# FOC_Driver.net
KiCad netlist of a schematic drawn in Altium Designer
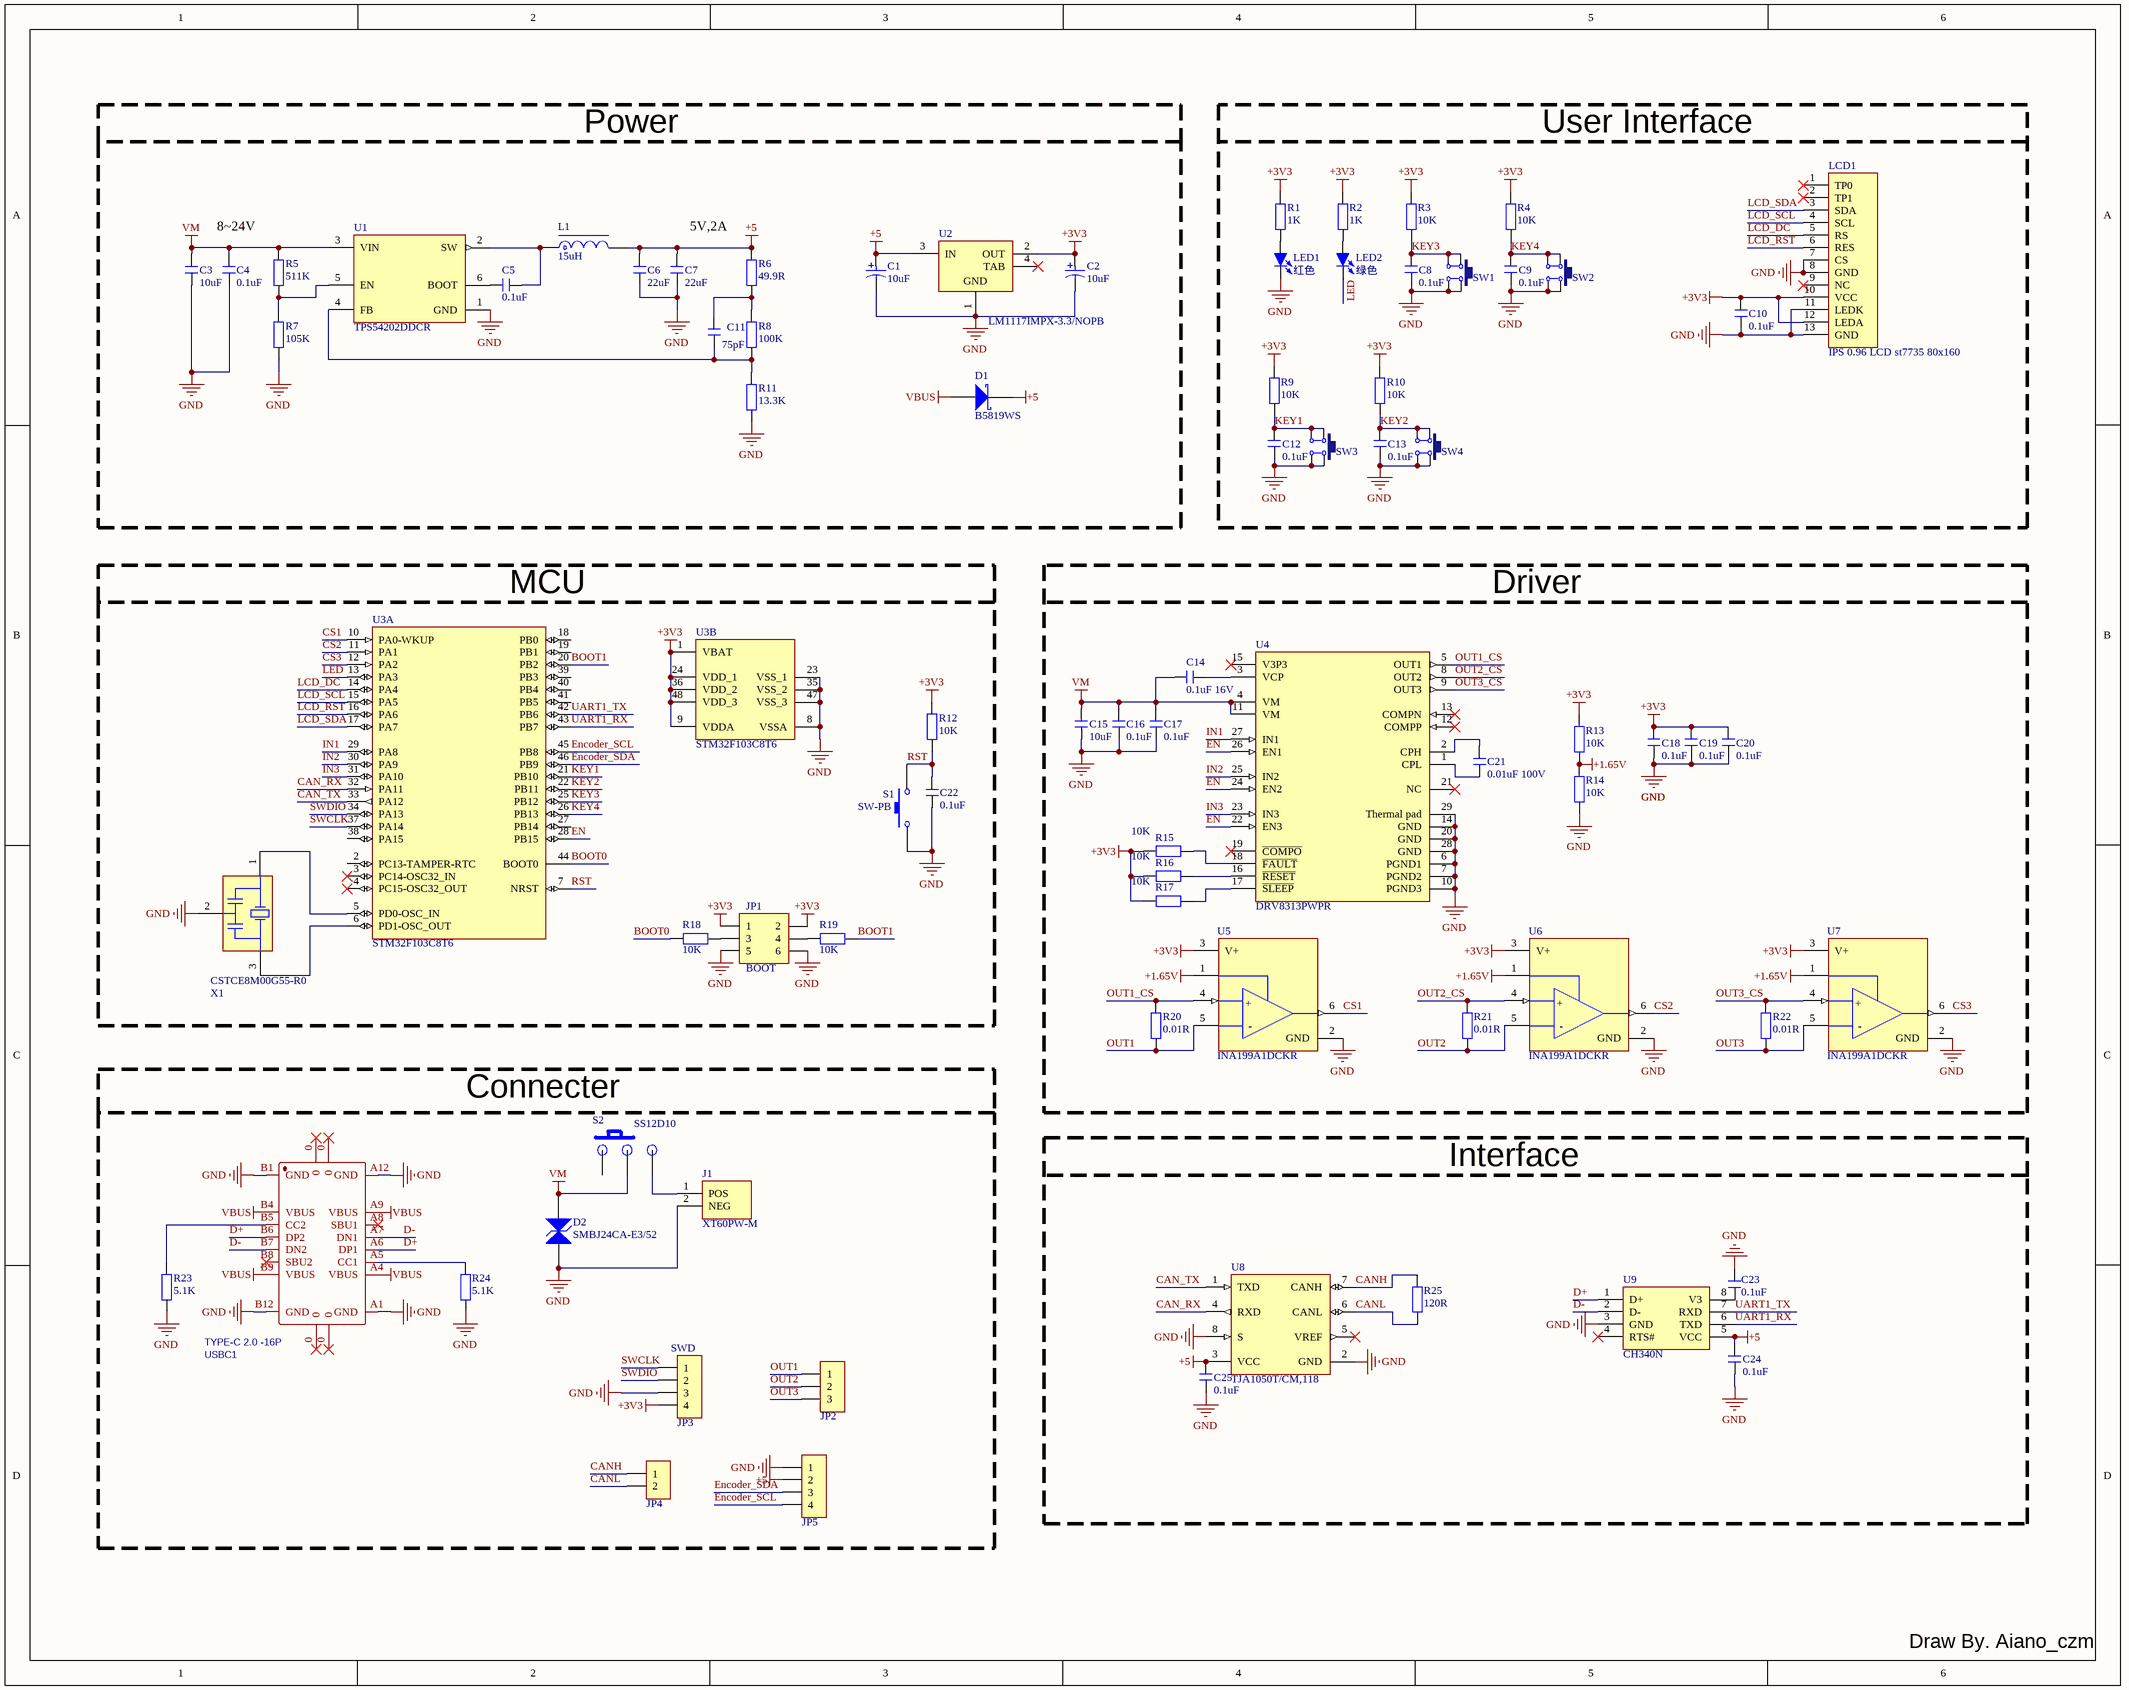
[diagram p0: FOC_Driver.SchDoc]

(export (version "E")
  (design (tool "Eeschema 10.0.6"))
  (components
    (comp (ref "C1")
      (value "10uF")
      (footprint "CAPMP3217X18-T_V")
      (description "Standard Tantalum, 10 uF, +/- 10%, 16 V, -55 to 125 degC, 2-Pin SMD (1206), RoHS, Tape and Reel")
      (libsource (lib "Altium Content Vault") (part "CAP-P-2"))
    )
    (comp (ref "C2")
      (value "10uF")
      (footprint "CAPMP3217X18-T_V")
      (description "Standard Tantalum, 10 uF, +/- 10%, 16 V, -55 to 125 degC, 2-Pin SMD (1206), RoHS, Tape and Reel")
      (libsource (lib "Altium Content Vault") (part "CAP-P-2"))
    )
    (comp (ref "C3")
      (value "10uF")
      (footprint "C 1206_M")
      (description "贴片电容")
      (libsource (lib "0.1 - 电阻-电容-电感") (part "C"))
    )
    (comp (ref "C4")
      (value "0.1uF")
      (footprint "C 0603_M")
      (description "贴片电容")
      (libsource (lib "0.1 - 电阻-电容-电感") (part "C"))
    )
    (comp (ref "C5")
      (value "0.1uF")
      (footprint "C 0603_M")
      (description "贴片电容")
      (libsource (lib "0.1 - 电阻-电容-电感") (part "C"))
    )
    (comp (ref "C6")
      (value "22uF")
      (footprint "C 1206_M")
      (description "贴片电容")
      (libsource (lib "0.1 - 电阻-电容-电感") (part "C"))
    )
    (comp (ref "C7")
      (value "22uF")
      (footprint "C 1206_M")
      (description "贴片电容")
      (libsource (lib "0.1 - 电阻-电容-电感") (part "C"))
    )
    (comp (ref "C8")
      (value "0.1uF")
      (footprint "C 0603_M")
      (description "贴片电容")
      (libsource (lib "0.1 - 电阻-电容-电感") (part "C"))
    )
    (comp (ref "C9")
      (value "0.1uF")
      (footprint "C 0603_M")
      (description "贴片电容")
      (libsource (lib "0.1 - 电阻-电容-电感") (part "C"))
    )
    (comp (ref "C10")
      (value "0.1uF")
      (footprint "C 0603_M")
      (description "贴片电容")
      (libsource (lib "0.1 - 电阻-电容-电感") (part "C"))
    )
    (comp (ref "C11")
      (value "75pF")
      (footprint "C 0603_M")
      (description "贴片电容")
      (libsource (lib "0.1 - 电阻-电容-电感") (part "C"))
    )
    (comp (ref "C12")
      (value "0.1uF")
      (footprint "C 0603_M")
      (description "贴片电容")
      (libsource (lib "0.1 - 电阻-电容-电感") (part "C"))
    )
    (comp (ref "C13")
      (value "0.1uF")
      (footprint "C 0603_M")
      (description "贴片电容")
      (libsource (lib "0.1 - 电阻-电容-电感") (part "C"))
    )
    (comp (ref "C14")
      (value "0.1uF 16V")
      (footprint "C 0603_M")
      (description "贴片电容")
      (libsource (lib "0.1 - 电阻-电容-电感") (part "C"))
    )
    (comp (ref "C15")
      (value "10uF")
      (footprint "C 1206_M")
      (description "贴片电容")
      (libsource (lib "0.1 - 电阻-电容-电感") (part "C"))
    )
    (comp (ref "C16")
      (value "0.1uF")
      (footprint "C 0603_M")
      (description "贴片电容")
      (libsource (lib "0.1 - 电阻-电容-电感") (part "C"))
    )
    (comp (ref "C17")
      (value "0.1uF")
      (footprint "C 0603_M")
      (description "贴片电容")
      (libsource (lib "0.1 - 电阻-电容-电感") (part "C"))
    )
    (comp (ref "C18")
      (value "0.1uF")
      (footprint "C 0603_M")
      (description "贴片电容")
      (libsource (lib "0.1 - 电阻-电容-电感") (part "C"))
    )
    (comp (ref "C19")
      (value "0.1uF")
      (footprint "C 0603_M")
      (description "贴片电容")
      (libsource (lib "0.1 - 电阻-电容-电感") (part "C"))
    )
    (comp (ref "C20")
      (value "0.1uF")
      (footprint "C 0603_M")
      (description "贴片电容")
      (libsource (lib "0.1 - 电阻-电容-电感") (part "C"))
    )
    (comp (ref "C21")
      (value "0.01uF 100V")
      (footprint "C 0603_M")
      (description "贴片电容")
      (libsource (lib "0.1 - 电阻-电容-电感") (part "C"))
    )
    (comp (ref "C22")
      (value "0.1uF")
      (footprint "C 0603_L")
      (description "贴片电容")
      (libsource (lib "0.1 - 电阻-电容-电感") (part "C"))
    )
    (comp (ref "C23")
      (value "0.1uF")
      (footprint "C 0603_M")
      (description "贴片电容")
      (libsource (lib "0.1 - 电阻-电容-电感") (part "C"))
    )
    (comp (ref "C24")
      (value "0.1uF")
      (footprint "C 0603_M")
      (description "贴片电容")
      (libsource (lib "0.1 - 电阻-电容-电感") (part "C"))
    )
    (comp (ref "C25")
      (value "0.1uF")
      (footprint "C 0603_M")
      (description "贴片电容")
      (libsource (lib "0.1 - 电阻-电容-电感") (part "C"))
    )
    (comp (ref "D1")
      (value "B5819WS")
      (footprint "SOD-323")
      (description "肖特基二极管")
      (libsource (lib "0.2 - 二极管-整流桥") (part "1N5819"))
    )
    (comp (ref "D2")
      (value "SMBJ24CA-E3/52")
      (footprint "VISH-DO-214AA-A-2_V")
      (fields (field (name "MANUFACTURER") "Vishay"))
      (libsource (lib "Altium Content Vault") (part "DZEN-AA-2"))
    )
    (comp (ref "J1")
      (value "XT60PW-M")
      (footprint "AMASS_XT60PW-M")
      (description "Socket, DC supply, male, PIN: 2")
      (fields (field (name "MF") "AMASS"))
      (libsource (lib "接插件") (part "XT60PW-M"))
    )
    (comp (ref "JP1")
      (value "BOOT")
      (footprint "HDR2.54-LI-2x3P")
      (description "3*2P接插件")
      (fields (field (name "版权归属") "封装库来自淘宝 ID：黄晶宝石"))
      (libsource (lib "5.4 - 接插件-脚距2.54 (100mil) ") (part "Header 3X2"))
    )
    (comp (ref "JP2")
      (value "HDR-1X3")
      (footprint "KF301-5.0-3P")
      (description "3P接插件")
      (fields (field (name "版权归属") "封装库来自淘宝 ID：黄晶宝石"))
      (libsource (lib "6.0 - 接插件-脚距5.0") (part "Header 3"))
    )
    (comp (ref "JP3")
      (value "SWD")
      (footprint "HDR2.54-LI-4P")
      (description "4P接插件")
      (fields (field (name "版权归属") "封装库来自淘宝 ID：黄晶宝石"))
      (libsource (lib "5.4 - 接插件-脚距2.54 (100mil) ") (part "Header 4"))
    )
    (comp (ref "JP4")
      (value "HDR-1X2")
      (footprint "KF301-5.0-2P")
      (description "2P接插件")
      (fields (field (name "版权归属") "封装库来自淘宝 ID：黄晶宝石"))
      (libsource (lib "6.0 - 接插件-脚距5.0") (part "Header 2"))
    )
    (comp (ref "JP5")
      (value "HDR-1X4")
      (footprint "HDR2.54-M-LI-4P")
      (description "4P接插件")
      (fields (field (name "版权归属") "封装库来自淘宝 ID：黄晶宝石"))
      (libsource (lib "5.4 - 接插件-脚距2.54 (100mil) ") (part "Header 4"))
    )
    (comp (ref "L1")
      (value "15uH")
      (footprint "CDRH73")
      (description "功率屏蔽电感")
      (fields (field (name "版权归属") "封装库来自淘宝 ID：黄晶宝石"))
      (libsource (lib "0.1 - 电阻-电容-电感") (part "L-CDRH"))
    )
    (comp (ref "LCD1")
      (value "IPS 0.96 LCD st7735 80x160")
      (footprint "IPS 0.96 LCD st7735 80x160")
      (description "中景园全彩IPS SPI接口 160x80 LCD显示屏")
      (libsource (lib "显示屏") (part "IPS 0.96 LCD st7735 80x160"))
    )
    (comp (ref "LED1")
      (value "红色")
      (footprint "LED 0603R")
      (description "贴片LED")
      (fields (field (name "版权归属") "封装库来自淘宝 ID：黄晶宝石"))
      (libsource (lib "0.3 - LED发光二极管") (part "LED-SMD"))
    )
    (comp (ref "LED2")
      (value "绿色")
      (footprint "LED 0603R")
      (description "贴片LED")
      (fields (field (name "版权归属") "封装库来自淘宝 ID：黄晶宝石"))
      (libsource (lib "0.3 - LED发光二极管") (part "LED-SMD"))
    )
    (comp (ref "R1")
      (value "1K")
      (footprint "R 0603_M")
      (description "贴片电阻")
      (fields (field (name "版权归属") "来自淘宝 ID：黄晶宝石"))
      (libsource (lib "0.1 - 电阻-电容-电感") (part "R"))
    )
    (comp (ref "R2")
      (value "1K")
      (footprint "R 0603_M")
      (description "贴片电阻")
      (fields (field (name "版权归属") "来自淘宝 ID：黄晶宝石"))
      (libsource (lib "0.1 - 电阻-电容-电感") (part "R"))
    )
    (comp (ref "R3")
      (value "10K")
      (footprint "R 0603_M")
      (description "贴片电阻")
      (fields (field (name "版权归属") "来自淘宝 ID：黄晶宝石"))
      (libsource (lib "0.1 - 电阻-电容-电感") (part "R"))
    )
    (comp (ref "R4")
      (value "10K")
      (footprint "R 0603_M")
      (description "贴片电阻")
      (fields (field (name "版权归属") "来自淘宝 ID：黄晶宝石"))
      (libsource (lib "0.1 - 电阻-电容-电感") (part "R"))
    )
    (comp (ref "R5")
      (value "511K")
      (footprint "R 0603_M")
      (description "贴片电阻")
      (fields (field (name "版权归属") "来自淘宝 ID：黄晶宝石"))
      (libsource (lib "0.1 - 电阻-电容-电感") (part "R"))
    )
    (comp (ref "R6")
      (value "49.9R")
      (footprint "R 0603_M")
      (description "贴片电阻")
      (fields (field (name "版权归属") "来自淘宝 ID：黄晶宝石"))
      (libsource (lib "0.1 - 电阻-电容-电感") (part "R"))
    )
    (comp (ref "R7")
      (value "105K")
      (footprint "R 0603_M")
      (description "贴片电阻")
      (fields (field (name "版权归属") "来自淘宝 ID：黄晶宝石"))
      (libsource (lib "0.1 - 电阻-电容-电感") (part "R"))
    )
    (comp (ref "R8")
      (value "100K")
      (footprint "R 0603_M")
      (description "贴片电阻")
      (fields (field (name "版权归属") "来自淘宝 ID：黄晶宝石"))
      (libsource (lib "0.1 - 电阻-电容-电感") (part "R"))
    )
    (comp (ref "R9")
      (value "10K")
      (footprint "R 0603_M")
      (description "贴片电阻")
      (fields (field (name "版权归属") "来自淘宝 ID：黄晶宝石"))
      (libsource (lib "0.1 - 电阻-电容-电感") (part "R"))
    )
    (comp (ref "R10")
      (value "10K")
      (footprint "R 0603_M")
      (description "贴片电阻")
      (fields (field (name "版权归属") "来自淘宝 ID：黄晶宝石"))
      (libsource (lib "0.1 - 电阻-电容-电感") (part "R"))
    )
    (comp (ref "R11")
      (value "13.3K")
      (footprint "R 0603_M")
      (description "贴片电阻")
      (fields (field (name "版权归属") "来自淘宝 ID：黄晶宝石"))
      (libsource (lib "0.1 - 电阻-电容-电感") (part "R"))
    )
    (comp (ref "R12")
      (value "10K")
      (footprint "R 0603_M")
      (description "贴片电阻")
      (fields (field (name "版权归属") "来自淘宝 ID：黄晶宝石"))
      (libsource (lib "0.1 - 电阻-电容-电感") (part "R"))
    )
    (comp (ref "R13")
      (value "10K")
      (footprint "R 0603_M")
      (description "贴片电阻")
      (fields (field (name "版权归属") "来自淘宝 ID：黄晶宝石"))
      (libsource (lib "0.1 - 电阻-电容-电感") (part "R"))
    )
    (comp (ref "R14")
      (value "10K")
      (footprint "R 0603_M")
      (description "贴片电阻")
      (fields (field (name "版权归属") "来自淘宝 ID：黄晶宝石"))
      (libsource (lib "0.1 - 电阻-电容-电感") (part "R"))
    )
    (comp (ref "R15")
      (value "10K")
      (footprint "R 0603_M")
      (description "贴片电阻")
      (fields (field (name "版权归属") "来自淘宝 ID：黄晶宝石"))
      (libsource (lib "0.1 - 电阻-电容-电感") (part "R"))
    )
    (comp (ref "R16")
      (value "10K")
      (footprint "R 0603_M")
      (description "贴片电阻")
      (fields (field (name "版权归属") "来自淘宝 ID：黄晶宝石"))
      (libsource (lib "0.1 - 电阻-电容-电感") (part "R"))
    )
    (comp (ref "R17")
      (value "10K")
      (footprint "R 0603_M")
      (description "贴片电阻")
      (fields (field (name "版权归属") "来自淘宝 ID：黄晶宝石"))
      (libsource (lib "0.1 - 电阻-电容-电感") (part "R"))
    )
    (comp (ref "R18")
      (value "10K")
      (footprint "R 0603_M")
      (description "贴片电阻")
      (fields (field (name "版权归属") "来自淘宝 ID：黄晶宝石"))
      (libsource (lib "0.1 - 电阻-电容-电感") (part "R"))
    )
    (comp (ref "R19")
      (value "10K")
      (footprint "R 0603_M")
      (description "贴片电阻")
      (fields (field (name "版权归属") "来自淘宝 ID：黄晶宝石"))
      (libsource (lib "0.1 - 电阻-电容-电感") (part "R"))
    )
    (comp (ref "R20")
      (value "0.01R")
      (footprint "R 0805_M")
      (description "贴片电阻")
      (fields (field (name "版权归属") "来自淘宝 ID：黄晶宝石"))
      (libsource (lib "0.1 - 电阻-电容-电感") (part "R"))
    )
    (comp (ref "R21")
      (value "0.01R")
      (footprint "R 0805_M")
      (description "贴片电阻")
      (fields (field (name "版权归属") "来自淘宝 ID：黄晶宝石"))
      (libsource (lib "0.1 - 电阻-电容-电感") (part "R"))
    )
    (comp (ref "R22")
      (value "0.01R")
      (footprint "R 0805_M")
      (description "贴片电阻")
      (fields (field (name "版权归属") "来自淘宝 ID：黄晶宝石"))
      (libsource (lib "0.1 - 电阻-电容-电感") (part "R"))
    )
    (comp (ref "R23")
      (value "5.1K")
      (footprint "R 0603_M")
      (description "贴片电阻")
      (fields (field (name "版权归属") "来自淘宝 ID：黄晶宝石"))
      (libsource (lib "0.1 - 电阻-电容-电感") (part "R"))
    )
    (comp (ref "R24")
      (value "5.1K")
      (footprint "R 0603_M")
      (description "贴片电阻")
      (fields (field (name "版权归属") "来自淘宝 ID：黄晶宝石"))
      (libsource (lib "0.1 - 电阻-电容-电感") (part "R"))
    )
    (comp (ref "R25")
      (value "120R")
      (footprint "R 0603_M")
      (description "贴片电阻")
      (fields (field (name "版权归属") "来自淘宝 ID：黄晶宝石"))
      (libsource (lib "0.1 - 电阻-电容-电感") (part "R"))
    )
    (comp (ref "S1")
      (value "SW-PB")
      (footprint "SW_PB2_A1")
      (description "微动开关")
      (fields (field (name "PUBLISHER") "Altium Limited"))
      (libsource (lib "0.7 - 常用按键-开关") (part "SW-PB"))
    )
    (comp (ref "S2")
      (value "SS12D10")
      (footprint "SS12D10")
      (description "大电流拨动开关 直脚")
      (libsource (lib "开关") (part "SS12D10"))
    )
    (comp (ref "SW1")
      (value "6x6x5")
      (footprint "TSW SMD-6*6*4.3")
      (description "贴片6x6轻触开关")
      (fields (field (name "版权归属") "封装库来自淘宝 ID：黄晶宝石"))
      (libsource (lib "0.7 - 常用按键-开关") (part "TSW SMD-6x6"))
    )
    (comp (ref "SW2")
      (value "6x6x5")
      (footprint "TSW SMD-6*6*4.3")
      (description "贴片6x6轻触开关")
      (fields (field (name "版权归属") "封装库来自淘宝 ID：黄晶宝石"))
      (libsource (lib "0.7 - 常用按键-开关") (part "TSW SMD-6x6"))
    )
    (comp (ref "SW3")
      (value "6x6x5")
      (footprint "TSW SMD-6*6*4.3")
      (description "贴片6x6轻触开关")
      (fields (field (name "版权归属") "封装库来自淘宝 ID：黄晶宝石"))
      (libsource (lib "0.7 - 常用按键-开关") (part "TSW SMD-6x6"))
    )
    (comp (ref "SW4")
      (value "6x6x5")
      (footprint "TSW SMD-6*6*4.3")
      (description "贴片6x6轻触开关")
      (fields (field (name "版权归属") "封装库来自淘宝 ID：黄晶宝石"))
      (libsource (lib "0.7 - 常用按键-开关") (part "TSW SMD-6x6"))
    )
    (comp (ref "U1")
      (value "TPS54202DDCR")
      (footprint "FP-DDC0006A-IPC_B")
      (description "IC REG BUCK ADJ 2A TSOT23-6")
      (libsource (lib "Altium Content Vault") (part "35c2d3f1afc239a386b2ba50eead654"))
    )
    (comp (ref "U2")
      (value "LM1117IMPX-3.3/NOPB")
      (footprint "MP04A_M")
      (description "800mA Low-Dropout Linear Regulator, 4-pin SOT-223, Pb-Free")
      (fields (field (name "MANUFACTURER") "National Semiconductor"))
      (libsource (lib "Altium Content Vault") (part "PM-REG-LM1086-SOT4"))
    )
    (comp (ref "U3")
      (value "STM32F103C8T6")
      (footprint "STM-LQFP48_M")
      (libsource (lib "Altium Content Vault") (part "MC-ARM-STM32F103X8_B-SQ48"))
    )
    (comp (ref "U4")
      (value "DRV8313PWPR")
      (footprint "FP-PWP0028C-IPC_B")
      (description "IC MOTOR DRIVER 8V-60V 28HTSSOP")
      (libsource (lib "Altium Content Vault") (part "6c5e8d1d79df7918d4eb9ae5de6b4b8"))
    )
    (comp (ref "U5")
      (value "INA199A1DCKR")
      (footprint "FP-DCK0006A-IPC_A")
      (description "IC OPAMP CURR SENSE 14KHZ SC70-6")
      (libsource (lib "Altium Content Vault") (part "e49a1c4e02aaa7cdc8fdf8d536a06ae"))
    )
    (comp (ref "U6")
      (value "INA199A1DCKR")
      (footprint "FP-DCK0006A-IPC_A")
      (description "IC OPAMP CURR SENSE 14KHZ SC70-6")
      (libsource (lib "Altium Content Vault") (part "e49a1c4e02aaa7cdc8fdf8d536a06ae"))
    )
    (comp (ref "U7")
      (value "INA199A1DCKR")
      (footprint "FP-DCK0006A-IPC_A")
      (description "IC OPAMP CURR SENSE 14KHZ SC70-6")
      (libsource (lib "Altium Content Vault") (part "e49a1c4e02aaa7cdc8fdf8d536a06ae"))
    )
    (comp (ref "U8")
      (value "TJA1050T/CM,118")
      (footprint "NXP-SOT96-1_M")
      (fields (field (name "MANUFACTURER") "NXP Semiconductors"))
      (libsource (lib "Altium Content Vault") (part "NXP-TJA1050-8"))
    )
    (comp (ref "U9") (value "CH340N") (footprint "CH340N") (libsource (lib "接口芯片") (part "CH340N")))
    (comp (ref "USBC1")
      (value "TYPE-C 2.0 -16P")
      (footprint "USB-C-SMD_TYPE-C-USB-5")
      (description "USB2.0 Type-C 母座 16Pin")
      (libsource (lib "0.8 - 以太网-音频-USB插座") (part "USB2.0 Type-C 16Pin母座"))
    )
    (comp (ref "X1")
      (value "CSTCE8M00G55-R0")
      (footprint "MURA-CSTCE_G_A-3_V")
      (description "Ceramic Resonator, 8 MHz, +/- 0.5%, -20 to 80 degC, 3-Pin SMD, RoHS, Tape and Reel")
      (fields (field (name "TOLERANCE") "0.5%") (field (name "MANUFACTURER") "Murata"))
      (libsource (lib "Altium Content Vault") (part "MURA-CSTCE_G_A-3"))
    )
  )
  (nets
    (net (code "1") (name "+1.65V") (class "Default")
      (node (ref "R13") (pin "1") (pinfunction "1_1") (pintype "passive"))
      (node (ref "R14") (pin "2") (pinfunction "2_2") (pintype "passive"))
      (node (ref "U5") (pin "1") (pinfunction "REF_1") (pintype "passive"))
      (node (ref "U6") (pin "1") (pinfunction "REF_1") (pintype "passive"))
      (node (ref "U7") (pin "1") (pinfunction "REF_1") (pintype "passive"))
    )
    (net (code "2") (name "+3V3") (class "Default")
      (node (ref "C10") (pin "2") (pinfunction "2_2") (pintype "passive"))
      (node (ref "C18") (pin "1") (pinfunction "1_1") (pintype "passive"))
      (node (ref "C19") (pin "1") (pinfunction "1_1") (pintype "passive"))
      (node (ref "C2") (pin "1") (pinfunction "1_1") (pintype "passive"))
      (node (ref "C20") (pin "1") (pinfunction "1_1") (pintype "passive"))
      (node (ref "JP1") (pin "1") (pinfunction "1_1") (pintype "passive"))
      (node (ref "JP1") (pin "2") (pinfunction "2_2") (pintype "passive"))
      (node (ref "JP3") (pin "4") (pinfunction "4_4") (pintype "passive"))
      (node (ref "LCD1") (pin "10") (pinfunction "VCC_10") (pintype "passive"))
      (node (ref "LCD1") (pin "12") (pinfunction "LEDA_12") (pintype "passive"))
      (node (ref "R1") (pin "1") (pinfunction "1_1") (pintype "passive"))
      (node (ref "R10") (pin "1") (pinfunction "1_1") (pintype "passive"))
      (node (ref "R12") (pin "2") (pinfunction "2_2") (pintype "passive"))
      (node (ref "R13") (pin "2") (pinfunction "2_2") (pintype "passive"))
      (node (ref "R15") (pin "2") (pinfunction "2_2") (pintype "passive"))
      (node (ref "R16") (pin "2") (pinfunction "2_2") (pintype "passive"))
      (node (ref "R17") (pin "2") (pinfunction "2_2") (pintype "passive"))
      (node (ref "R2") (pin "1") (pinfunction "1_1") (pintype "passive"))
      (node (ref "R3") (pin "1") (pinfunction "1_1") (pintype "passive"))
      (node (ref "R4") (pin "1") (pinfunction "1_1") (pintype "passive"))
      (node (ref "R9") (pin "1") (pinfunction "1_1") (pintype "passive"))
      (node (ref "U2") (pin "2") (pinfunction "OUT_2") (pintype "power_in"))
      (node (ref "U3") (pin "1") (pinfunction "VBAT_1") (pintype "power_in"))
      (node (ref "U3") (pin "24") (pinfunction "VDD_1_24") (pintype "power_in"))
      (node (ref "U3") (pin "36") (pinfunction "VDD_2_36") (pintype "power_in"))
      (node (ref "U3") (pin "48") (pinfunction "VDD_3_48") (pintype "power_in"))
      (node (ref "U3") (pin "9") (pinfunction "VDDA_9") (pintype "power_in"))
      (node (ref "U5") (pin "3") (pinfunction "V+_3") (pintype "power_in"))
      (node (ref "U6") (pin "3") (pinfunction "V+_3") (pintype "power_in"))
      (node (ref "U7") (pin "3") (pinfunction "V+_3") (pintype "power_in"))
    )
    (net (code "3") (name "+5") (class "Default")
      (node (ref "C1") (pin "1") (pinfunction "1_1") (pintype "passive"))
      (node (ref "C24") (pin "2") (pinfunction "2_2") (pintype "passive"))
      (node (ref "C25") (pin "1") (pinfunction "1_1") (pintype "passive"))
      (node (ref "C6") (pin "2") (pinfunction "2_2") (pintype "passive"))
      (node (ref "C7") (pin "2") (pinfunction "2_2") (pintype "passive"))
      (node (ref "D1") (pin "2") (pinfunction "K_2") (pintype "passive"))
      (node (ref "JP5") (pin "2") (pinfunction "2_2") (pintype "passive"))
      (node (ref "L1") (pin "2") (pinfunction "2_2") (pintype "passive"))
      (node (ref "R6") (pin "2") (pinfunction "2_2") (pintype "passive"))
      (node (ref "U2") (pin "3") (pinfunction "IN_3") (pintype "power_in"))
      (node (ref "U8") (pin "3") (pinfunction "VCC_3") (pintype "power_in"))
      (node (ref "U9") (pin "5") (pinfunction "VCC_5") (pintype "passive"))
    )
    (net (code "4") (name "/BOOT0") (class "Default")
      (node (ref "R18") (pin "2") (pinfunction "2_2") (pintype "passive"))
      (node (ref "U3") (pin "44") (pinfunction "BOOT0_44") (pintype "passive"))
    )
    (net (code "5") (name "/BOOT1") (class "Default")
      (node (ref "R19") (pin "1") (pinfunction "1_1") (pintype "passive"))
      (node (ref "U3") (pin "20") (pinfunction "PB2_20") (pintype "bidirectional"))
    )
    (net (code "6") (name "/CANH") (class "Default")
      (node (ref "JP4") (pin "1") (pinfunction "1_1") (pintype "passive"))
      (node (ref "R25") (pin "2") (pinfunction "2_2") (pintype "passive"))
      (node (ref "U8") (pin "7") (pinfunction "CANH_7") (pintype "bidirectional"))
    )
    (net (code "7") (name "/CANL") (class "Default")
      (node (ref "JP4") (pin "2") (pinfunction "2_2") (pintype "passive"))
      (node (ref "R25") (pin "1") (pinfunction "1_1") (pintype "passive"))
      (node (ref "U8") (pin "6") (pinfunction "CANL_6") (pintype "bidirectional"))
    )
    (net (code "8") (name "/CAN_RX") (class "Default")
      (node (ref "U3") (pin "32") (pinfunction "PA11_32") (pintype "input"))
      (node (ref "U8") (pin "4") (pinfunction "RXD_4") (pintype "output"))
    )
    (net (code "9") (name "/CAN_TX") (class "Default")
      (node (ref "U3") (pin "33") (pinfunction "PA12_33") (pintype "output"))
      (node (ref "U8") (pin "1") (pinfunction "TXD_1") (pintype "input"))
    )
    (net (code "10") (name "/CS1") (class "Default")
      (node (ref "U3") (pin "10") (pinfunction "PA0-WKUP_10") (pintype "input"))
      (node (ref "U5") (pin "6") (pinfunction "OUT_6") (pintype "output"))
    )
    (net (code "11") (name "/CS2") (class "Default")
      (node (ref "U3") (pin "11") (pinfunction "PA1_11") (pintype "input"))
      (node (ref "U6") (pin "6") (pinfunction "OUT_6") (pintype "output"))
    )
    (net (code "12") (name "/CS3") (class "Default")
      (node (ref "U3") (pin "12") (pinfunction "PA2_12") (pintype "input"))
      (node (ref "U7") (pin "6") (pinfunction "OUT_6") (pintype "output"))
    )
    (net (code "13") (name "/D+") (class "Default")
      (node (ref "U9") (pin "1") (pinfunction "D+_1") (pintype "passive"))
      (node (ref "USBC1") (pin "A6") (pinfunction "DP1_A6") (pintype "passive"))
      (node (ref "USBC1") (pin "B6") (pinfunction "DP2_B6") (pintype "passive"))
    )
    (net (code "14") (name "/D-") (class "Default")
      (node (ref "U9") (pin "2") (pinfunction "D-_2") (pintype "passive"))
      (node (ref "USBC1") (pin "A7") (pinfunction "DN1_A7") (pintype "passive"))
      (node (ref "USBC1") (pin "B7") (pinfunction "DN2_B7") (pintype "passive"))
    )
    (net (code "15") (name "/EN") (class "Default")
      (node (ref "U3") (pin "28") (pinfunction "PB15_28") (pintype "bidirectional"))
      (node (ref "U4") (pin "22") (pinfunction "EN3_22") (pintype "input"))
      (node (ref "U4") (pin "24") (pinfunction "EN2_24") (pintype "input"))
      (node (ref "U4") (pin "26") (pinfunction "EN1_26") (pintype "input"))
    )
    (net (code "16") (name "/Encoder_SCL") (class "Default")
      (node (ref "JP5") (pin "4") (pinfunction "4_4") (pintype "passive"))
      (node (ref "U3") (pin "45") (pinfunction "PB8_45") (pintype "bidirectional"))
    )
    (net (code "17") (name "/Encoder_SDA") (class "Default")
      (node (ref "JP5") (pin "3") (pinfunction "3_3") (pintype "passive"))
      (node (ref "U3") (pin "46") (pinfunction "PB9_46") (pintype "bidirectional"))
    )
    (net (code "18") (name "/IN1") (class "Default")
      (node (ref "U3") (pin "29") (pinfunction "PA8_29") (pintype "bidirectional"))
      (node (ref "U4") (pin "27") (pinfunction "IN1_27") (pintype "input"))
    )
    (net (code "19") (name "/IN2") (class "Default")
      (node (ref "U3") (pin "30") (pinfunction "PA9_30") (pintype "bidirectional"))
      (node (ref "U4") (pin "25") (pinfunction "IN2_25") (pintype "input"))
    )
    (net (code "20") (name "/IN3") (class "Default")
      (node (ref "U3") (pin "31") (pinfunction "PA10_31") (pintype "bidirectional"))
      (node (ref "U4") (pin "23") (pinfunction "IN3_23") (pintype "input"))
    )
    (net (code "21") (name "/KEY1") (class "Default")
      (node (ref "C12") (pin "1") (pinfunction "1_1") (pintype "passive"))
      (node (ref "R9") (pin "2") (pinfunction "2_2") (pintype "passive"))
      (node (ref "SW3") (pin "1") (pinfunction "1_1") (pintype "passive"))
      (node (ref "SW3") (pin "4") (pinfunction "4_4") (pintype "passive"))
      (node (ref "U3") (pin "21") (pinfunction "PB10_21") (pintype "bidirectional"))
    )
    (net (code "22") (name "/KEY2") (class "Default")
      (node (ref "C13") (pin "1") (pinfunction "1_1") (pintype "passive"))
      (node (ref "R10") (pin "2") (pinfunction "2_2") (pintype "passive"))
      (node (ref "SW4") (pin "1") (pinfunction "1_1") (pintype "passive"))
      (node (ref "SW4") (pin "4") (pinfunction "4_4") (pintype "passive"))
      (node (ref "U3") (pin "22") (pinfunction "PB11_22") (pintype "bidirectional"))
    )
    (net (code "23") (name "/KEY3") (class "Default")
      (node (ref "C8") (pin "1") (pinfunction "1_1") (pintype "passive"))
      (node (ref "R3") (pin "2") (pinfunction "2_2") (pintype "passive"))
      (node (ref "SW1") (pin "1") (pinfunction "1_1") (pintype "passive"))
      (node (ref "SW1") (pin "4") (pinfunction "4_4") (pintype "passive"))
      (node (ref "U3") (pin "25") (pinfunction "PB12_25") (pintype "bidirectional"))
    )
    (net (code "24") (name "/KEY4") (class "Default")
      (node (ref "C9") (pin "1") (pinfunction "1_1") (pintype "passive"))
      (node (ref "R4") (pin "2") (pinfunction "2_2") (pintype "passive"))
      (node (ref "SW2") (pin "1") (pinfunction "1_1") (pintype "passive"))
      (node (ref "SW2") (pin "4") (pinfunction "4_4") (pintype "passive"))
      (node (ref "U3") (pin "26") (pinfunction "PB13_26") (pintype "bidirectional"))
    )
    (net (code "25") (name "/LCD_DC") (class "Default")
      (node (ref "LCD1") (pin "5") (pinfunction "RS_5") (pintype "passive"))
      (node (ref "U3") (pin "14") (pinfunction "PA4_14") (pintype "bidirectional"))
    )
    (net (code "26") (name "/LCD_RST") (class "Default")
      (node (ref "LCD1") (pin "6") (pinfunction "RES_6") (pintype "passive"))
      (node (ref "U3") (pin "16") (pinfunction "PA6_16") (pintype "bidirectional"))
    )
    (net (code "27") (name "/LCD_SCL") (class "Default")
      (node (ref "LCD1") (pin "4") (pinfunction "SCL_4") (pintype "passive"))
      (node (ref "U3") (pin "15") (pinfunction "PA5_15") (pintype "bidirectional"))
    )
    (net (code "28") (name "/LCD_SDA") (class "Default")
      (node (ref "LCD1") (pin "3") (pinfunction "SDA_3") (pintype "passive"))
      (node (ref "U3") (pin "17") (pinfunction "PA7_17") (pintype "bidirectional"))
    )
    (net (code "29") (name "/LED") (class "Default")
      (node (ref "LED2") (pin "2") (pinfunction "K_2") (pintype "passive"))
      (node (ref "U3") (pin "13") (pinfunction "PA3_13") (pintype "bidirectional"))
    )
    (net (code "30") (name "/OUT1") (class "Default")
      (node (ref "JP2") (pin "1") (pinfunction "1_1") (pintype "passive"))
      (node (ref "R20") (pin "1") (pinfunction "1_1") (pintype "passive"))
      (node (ref "U5") (pin "5") (pinfunction "IN-_5") (pintype "passive"))
    )
    (net (code "31") (name "/OUT1_CS") (class "Default")
      (node (ref "R20") (pin "2") (pinfunction "2_2") (pintype "passive"))
      (node (ref "U4") (pin "5") (pinfunction "OUT1_5") (pintype "output"))
      (node (ref "U5") (pin "4") (pinfunction "IN+_4") (pintype "input"))
    )
    (net (code "32") (name "/OUT2") (class "Default")
      (node (ref "JP2") (pin "2") (pinfunction "2_2") (pintype "passive"))
      (node (ref "R21") (pin "1") (pinfunction "1_1") (pintype "passive"))
      (node (ref "U6") (pin "5") (pinfunction "IN-_5") (pintype "passive"))
    )
    (net (code "33") (name "/OUT2_CS") (class "Default")
      (node (ref "R21") (pin "2") (pinfunction "2_2") (pintype "passive"))
      (node (ref "U4") (pin "8") (pinfunction "OUT2_8") (pintype "output"))
      (node (ref "U6") (pin "4") (pinfunction "IN+_4") (pintype "input"))
    )
    (net (code "34") (name "/OUT3") (class "Default")
      (node (ref "JP2") (pin "3") (pinfunction "3_3") (pintype "passive"))
      (node (ref "R22") (pin "1") (pinfunction "1_1") (pintype "passive"))
      (node (ref "U7") (pin "5") (pinfunction "IN-_5") (pintype "passive"))
    )
    (net (code "35") (name "/OUT3_CS") (class "Default")
      (node (ref "R22") (pin "2") (pinfunction "2_2") (pintype "passive"))
      (node (ref "U4") (pin "9") (pinfunction "OUT3_9") (pintype "output"))
      (node (ref "U7") (pin "4") (pinfunction "IN+_4") (pintype "input"))
    )
    (net (code "36") (name "/RST") (class "Default")
      (node (ref "C22") (pin "2") (pinfunction "2_2") (pintype "passive"))
      (node (ref "R12") (pin "1") (pinfunction "1_1") (pintype "passive"))
      (node (ref "S1") (pin "2") (pinfunction "2_2") (pintype "passive"))
      (node (ref "U3") (pin "7") (pinfunction "NRST_7") (pintype "bidirectional"))
    )
    (net (code "37") (name "/SWCLK") (class "Default")
      (node (ref "JP3") (pin "1") (pinfunction "1_1") (pintype "passive"))
      (node (ref "U3") (pin "37") (pinfunction "PA14_37") (pintype "bidirectional"))
    )
    (net (code "38") (name "/SWDIO") (class "Default")
      (node (ref "JP3") (pin "2") (pinfunction "2_2") (pintype "passive"))
      (node (ref "U3") (pin "34") (pinfunction "PA13_34") (pintype "bidirectional"))
    )
    (net (code "39") (name "/UART1_RX") (class "Default")
      (node (ref "U3") (pin "43") (pinfunction "PB7_43") (pintype "bidirectional"))
      (node (ref "U9") (pin "6") (pinfunction "TXD_6") (pintype "passive"))
    )
    (net (code "40") (name "/UART1_TX") (class "Default")
      (node (ref "U3") (pin "42") (pinfunction "PB6_42") (pintype "bidirectional"))
      (node (ref "U9") (pin "7") (pinfunction "RXD_7") (pintype "passive"))
    )
    (net (code "41") (name "GND") (class "Default")
      (node (ref "C1") (pin "2") (pinfunction "2_2") (pintype "passive"))
      (node (ref "C10") (pin "1") (pinfunction "1_1") (pintype "passive"))
      (node (ref "C12") (pin "2") (pinfunction "2_2") (pintype "passive"))
      (node (ref "C13") (pin "2") (pinfunction "2_2") (pintype "passive"))
      (node (ref "C15") (pin "1") (pinfunction "1_1") (pintype "passive"))
      (node (ref "C16") (pin "1") (pinfunction "1_1") (pintype "passive"))
      (node (ref "C17") (pin "1") (pinfunction "1_1") (pintype "passive"))
      (node (ref "C18") (pin "2") (pinfunction "2_2") (pintype "passive"))
      (node (ref "C19") (pin "2") (pinfunction "2_2") (pintype "passive"))
      (node (ref "C2") (pin "2") (pinfunction "2_2") (pintype "passive"))
      (node (ref "C20") (pin "2") (pinfunction "2_2") (pintype "passive"))
      (node (ref "C22") (pin "1") (pinfunction "1_1") (pintype "passive"))
      (node (ref "C23") (pin "2") (pinfunction "2_2") (pintype "passive"))
      (node (ref "C24") (pin "1") (pinfunction "1_1") (pintype "passive"))
      (node (ref "C25") (pin "2") (pinfunction "2_2") (pintype "passive"))
      (node (ref "C3") (pin "1") (pinfunction "1_1") (pintype "passive"))
      (node (ref "C4") (pin "1") (pinfunction "1_1") (pintype "passive"))
      (node (ref "C6") (pin "1") (pinfunction "1_1") (pintype "passive"))
      (node (ref "C7") (pin "1") (pinfunction "1_1") (pintype "passive"))
      (node (ref "C8") (pin "2") (pinfunction "2_2") (pintype "passive"))
      (node (ref "C9") (pin "2") (pinfunction "2_2") (pintype "passive"))
      (node (ref "D2") (pin "1") (pinfunction "A_1") (pintype "passive"))
      (node (ref "J1") (pin "2") (pinfunction "NEG_2") (pintype "passive"))
      (node (ref "JP1") (pin "5") (pinfunction "5_5") (pintype "passive"))
      (node (ref "JP1") (pin "6") (pinfunction "6_6") (pintype "passive"))
      (node (ref "JP3") (pin "3") (pinfunction "3_3") (pintype "passive"))
      (node (ref "JP5") (pin "1") (pinfunction "1_1") (pintype "passive"))
      (node (ref "LCD1") (pin "11") (pinfunction "LEDK_11") (pintype "passive"))
      (node (ref "LCD1") (pin "13") (pinfunction "GND_13") (pintype "passive"))
      (node (ref "LCD1") (pin "7") (pinfunction "CS_7") (pintype "passive"))
      (node (ref "LCD1") (pin "8") (pinfunction "GND_8") (pintype "passive"))
      (node (ref "LED1") (pin "2") (pinfunction "K_2") (pintype "passive"))
      (node (ref "R11") (pin "1") (pinfunction "1_1") (pintype "passive"))
      (node (ref "R14") (pin "1") (pinfunction "1_1") (pintype "passive"))
      (node (ref "R23") (pin "1") (pinfunction "1_1") (pintype "passive"))
      (node (ref "R24") (pin "1") (pinfunction "1_1") (pintype "passive"))
      (node (ref "R7") (pin "1") (pinfunction "1_1") (pintype "passive"))
      (node (ref "S1") (pin "1") (pinfunction "1_1") (pintype "passive"))
      (node (ref "SW1") (pin "2") (pinfunction "2_2") (pintype "passive"))
      (node (ref "SW1") (pin "3") (pinfunction "3_3") (pintype "passive"))
      (node (ref "SW2") (pin "2") (pinfunction "2_2") (pintype "passive"))
      (node (ref "SW2") (pin "3") (pinfunction "3_3") (pintype "passive"))
      (node (ref "SW3") (pin "2") (pinfunction "2_2") (pintype "passive"))
      (node (ref "SW3") (pin "3") (pinfunction "3_3") (pintype "passive"))
      (node (ref "SW4") (pin "2") (pinfunction "2_2") (pintype "passive"))
      (node (ref "SW4") (pin "3") (pinfunction "3_3") (pintype "passive"))
      (node (ref "U1") (pin "1") (pinfunction "GND_1") (pintype "power_in"))
      (node (ref "U2") (pin "1") (pinfunction "GND_1") (pintype "power_in"))
      (node (ref "U3") (pin "23") (pinfunction "VSS_1_23") (pintype "power_in"))
      (node (ref "U3") (pin "35") (pinfunction "VSS_2_35") (pintype "power_in"))
      (node (ref "U3") (pin "47") (pinfunction "VSS_3_47") (pintype "power_in"))
      (node (ref "U3") (pin "8") (pinfunction "VSSA_8") (pintype "power_in"))
      (node (ref "U4") (pin "10") (pinfunction "PGND3_10") (pintype "power_in"))
      (node (ref "U4") (pin "14") (pinfunction "GND_14") (pintype "power_in"))
      (node (ref "U4") (pin "20") (pinfunction "GND_20") (pintype "power_in"))
      (node (ref "U4") (pin "28") (pinfunction "GND_28") (pintype "power_in"))
      (node (ref "U4") (pin "29") (pinfunction "Thermal_pad_29") (pintype "power_in"))
      (node (ref "U4") (pin "6") (pinfunction "PGND1_6") (pintype "power_in"))
      (node (ref "U4") (pin "7") (pinfunction "PGND2_7") (pintype "power_in"))
      (node (ref "U5") (pin "2") (pinfunction "GND_2") (pintype "power_in"))
      (node (ref "U6") (pin "2") (pinfunction "GND_2") (pintype "power_in"))
      (node (ref "U7") (pin "2") (pinfunction "GND_2") (pintype "power_in"))
      (node (ref "U8") (pin "2") (pinfunction "GND_2") (pintype "power_in"))
      (node (ref "U8") (pin "8") (pinfunction "S_8") (pintype "input"))
      (node (ref "U9") (pin "3") (pinfunction "GND_3") (pintype "passive"))
      (node (ref "USBC1") (pin "A1") (pinfunction "GND_A1") (pintype "passive"))
      (node (ref "USBC1") (pin "A12") (pinfunction "GND_A12") (pintype "passive"))
      (node (ref "USBC1") (pin "B1") (pinfunction "GND_B1") (pintype "passive"))
      (node (ref "USBC1") (pin "B12") (pinfunction "GND_B12") (pintype "passive"))
      (node (ref "X1") (pin "2") (pinfunction "GND_2") (pintype "power_in"))
    )
    (net (code "42") (name "Net-(C11-Pad2)") (class "Default")
      (node (ref "C11") (pin "2") (pinfunction "2_2") (pintype "passive"))
      (node (ref "R6") (pin "1") (pinfunction "1_1") (pintype "passive"))
      (node (ref "R8") (pin "2") (pinfunction "2_2") (pintype "passive"))
    )
    (net (code "43") (name "Net-(J1-POS)") (class "Default")
      (node (ref "J1") (pin "1") (pinfunction "POS_1") (pintype "passive"))
      (node (ref "S2") (pin "3") (pinfunction "3_3") (pintype "passive"))
    )
    (net (code "44") (name "Net-(JP1-Pad3)") (class "Default")
      (node (ref "JP1") (pin "3") (pinfunction "3_3") (pintype "passive"))
      (node (ref "R18") (pin "1") (pinfunction "1_1") (pintype "passive"))
    )
    (net (code "45") (name "Net-(JP1-Pad4)") (class "Default")
      (node (ref "JP1") (pin "4") (pinfunction "4_4") (pintype "passive"))
      (node (ref "R19") (pin "2") (pinfunction "2_2") (pintype "passive"))
    )
    (net (code "46") (name "Net-(LED1-A)") (class "Default")
      (node (ref "LED1") (pin "1") (pinfunction "A_1") (pintype "passive"))
      (node (ref "R1") (pin "2") (pinfunction "2_2") (pintype "passive"))
    )
    (net (code "47") (name "Net-(LED2-A)") (class "Default")
      (node (ref "LED2") (pin "1") (pinfunction "A_1") (pintype "passive"))
      (node (ref "R2") (pin "2") (pinfunction "2_2") (pintype "passive"))
    )
    (net (code "48") (name "Net-(U1-BOOT)") (class "Default")
      (node (ref "C5") (pin "1") (pinfunction "1_1") (pintype "passive"))
      (node (ref "U1") (pin "6") (pinfunction "BOOT_6") (pintype "passive"))
    )
    (net (code "49") (name "Net-(U1-EN)") (class "Default")
      (node (ref "R5") (pin "1") (pinfunction "1_1") (pintype "passive"))
      (node (ref "R7") (pin "2") (pinfunction "2_2") (pintype "passive"))
      (node (ref "U1") (pin "5") (pinfunction "EN_5") (pintype "passive"))
    )
    (net (code "50") (name "Net-(U1-FB)") (class "Default")
      (node (ref "C11") (pin "1") (pinfunction "1_1") (pintype "passive"))
      (node (ref "R11") (pin "2") (pinfunction "2_2") (pintype "passive"))
      (node (ref "R8") (pin "1") (pinfunction "1_1") (pintype "passive"))
      (node (ref "U1") (pin "4") (pinfunction "FB_4") (pintype "passive"))
    )
    (net (code "51") (name "Net-(U1-SW)") (class "Default")
      (node (ref "C5") (pin "2") (pinfunction "2_2") (pintype "passive"))
      (node (ref "L1") (pin "1") (pinfunction "1_1") (pintype "passive"))
      (node (ref "U1") (pin "2") (pinfunction "SW_2") (pintype "output"))
    )
    (net (code "52") (name "Net-(U3A-PD0-OSC_IN)") (class "Default")
      (node (ref "U3") (pin "5") (pinfunction "PD0-OSC_IN_5") (pintype "bidirectional"))
      (node (ref "X1") (pin "1") (pinfunction "X1_1") (pintype "passive"))
    )
    (net (code "53") (name "Net-(U3A-PD1-OSC_OUT)") (class "Default")
      (node (ref "U3") (pin "6") (pinfunction "PD1-OSC_OUT_6") (pintype "bidirectional"))
      (node (ref "X1") (pin "3") (pinfunction "X2_3") (pintype "passive"))
    )
    (net (code "54") (name "Net-(U4-CPH)") (class "Default")
      (node (ref "C21") (pin "2") (pinfunction "2_2") (pintype "passive"))
      (node (ref "U4") (pin "2") (pinfunction "CPH_2") (pintype "power_in"))
    )
    (net (code "55") (name "Net-(U4-CPL)") (class "Default")
      (node (ref "C21") (pin "1") (pinfunction "1_1") (pintype "passive"))
      (node (ref "U4") (pin "1") (pinfunction "CPL_1") (pintype "power_in"))
    )
    (net (code "56") (name "Net-(U4-VCP)") (class "Default")
      (node (ref "C14") (pin "1") (pinfunction "1_1") (pintype "passive"))
      (node (ref "U4") (pin "3") (pinfunction "VCP_3") (pintype "power_in"))
    )
    (net (code "57") (name "Net-(U4-~{FAULT})") (class "Default")
      (node (ref "R15") (pin "1") (pinfunction "1_1") (pintype "passive"))
      (node (ref "U4") (pin "18") (pinfunction "~{FAULT}_18") (pintype "open_collector"))
    )
    (net (code "58") (name "Net-(U4-~{RESET})") (class "Default")
      (node (ref "R16") (pin "1") (pinfunction "1_1") (pintype "passive"))
      (node (ref "U4") (pin "16") (pinfunction "~{RESET}_16") (pintype "passive"))
    )
    (net (code "59") (name "Net-(U4-~{SLEEP})") (class "Default")
      (node (ref "R17") (pin "1") (pinfunction "1_1") (pintype "passive"))
      (node (ref "U4") (pin "17") (pinfunction "~{SLEEP}_17") (pintype "passive"))
    )
    (net (code "60") (name "Net-(U9-V3)") (class "Default")
      (node (ref "C23") (pin "1") (pinfunction "1_1") (pintype "passive"))
      (node (ref "U9") (pin "8") (pinfunction "V3_8") (pintype "passive"))
    )
    (net (code "61") (name "Net-(USBC1-CC1)") (class "Default")
      (node (ref "R24") (pin "2") (pinfunction "2_2") (pintype "passive"))
      (node (ref "USBC1") (pin "A5") (pinfunction "CC1_A5") (pintype "passive"))
    )
    (net (code "62") (name "Net-(USBC1-CC2)") (class "Default")
      (node (ref "R23") (pin "2") (pinfunction "2_2") (pintype "passive"))
      (node (ref "USBC1") (pin "B5") (pinfunction "CC2_B5") (pintype "passive"))
    )
    (net (code "63") (name "VBUS") (class "Default")
      (node (ref "D1") (pin "1") (pinfunction "A_1") (pintype "passive"))
      (node (ref "USBC1") (pin "A4") (pinfunction "VBUS_A4") (pintype "passive"))
      (node (ref "USBC1") (pin "A9") (pinfunction "VBUS_A9") (pintype "passive"))
      (node (ref "USBC1") (pin "B4") (pinfunction "VBUS_B4") (pintype "passive"))
      (node (ref "USBC1") (pin "B9") (pinfunction "VBUS_B9") (pintype "passive"))
    )
    (net (code "64") (name "VM") (class "Default")
      (node (ref "C14") (pin "2") (pinfunction "2_2") (pintype "passive"))
      (node (ref "C15") (pin "2") (pinfunction "2_2") (pintype "passive"))
      (node (ref "C16") (pin "2") (pinfunction "2_2") (pintype "passive"))
      (node (ref "C17") (pin "2") (pinfunction "2_2") (pintype "passive"))
      (node (ref "C3") (pin "2") (pinfunction "2_2") (pintype "passive"))
      (node (ref "C4") (pin "2") (pinfunction "2_2") (pintype "passive"))
      (node (ref "D2") (pin "2") (pinfunction "A_2") (pintype "passive"))
      (node (ref "R5") (pin "2") (pinfunction "2_2") (pintype "passive"))
      (node (ref "S2") (pin "2") (pinfunction "2_2") (pintype "passive"))
      (node (ref "U1") (pin "3") (pinfunction "VIN_3") (pintype "power_in"))
      (node (ref "U4") (pin "11") (pinfunction "VM_11") (pintype "power_in"))
      (node (ref "U4") (pin "4") (pinfunction "VM_4") (pintype "power_in"))
    )
    (net (code "65") (name "unconnected-(LCD1-NC-Pad9)") (class "Default")
      (node (ref "LCD1") (pin "9") (pinfunction "NC_9") (pintype "passive+no_connect"))
    )
    (net (code "66") (name "unconnected-(LCD1-TP0-Pad1)") (class "Default")
      (node (ref "LCD1") (pin "1") (pinfunction "TP0_1") (pintype "passive+no_connect"))
    )
    (net (code "67") (name "unconnected-(LCD1-TP1-Pad2)") (class "Default")
      (node (ref "LCD1") (pin "2") (pinfunction "TP1_2") (pintype "passive+no_connect"))
    )
    (net (code "68") (name "unconnected-(S2-Pad1)") (class "Default")
      (node (ref "S2") (pin "1") (pinfunction "1_1") (pintype "passive"))
    )
    (net (code "69") (name "unconnected-(U2-TAB-Pad4)") (class "Default")
      (node (ref "U2") (pin "4") (pinfunction "TAB_4") (pintype "power_in+no_connect"))
    )
    (net (code "70") (name "unconnected-(U3A-PA15-Pad38)") (class "Default")
      (node (ref "U3") (pin "38") (pinfunction "PA15_38") (pintype "bidirectional"))
    )
    (net (code "71") (name "unconnected-(U3A-PB0-Pad18)") (class "Default")
      (node (ref "U3") (pin "18") (pinfunction "PB0_18") (pintype "bidirectional"))
    )
    (net (code "72") (name "unconnected-(U3A-PB1-Pad19)") (class "Default")
      (node (ref "U3") (pin "19") (pinfunction "PB1_19") (pintype "bidirectional"))
    )
    (net (code "73") (name "unconnected-(U3A-PB3-Pad39)") (class "Default")
      (node (ref "U3") (pin "39") (pinfunction "PB3_39") (pintype "bidirectional"))
    )
    (net (code "74") (name "unconnected-(U3A-PB4-Pad40)") (class "Default")
      (node (ref "U3") (pin "40") (pinfunction "PB4_40") (pintype "bidirectional"))
    )
    (net (code "75") (name "unconnected-(U3A-PB5-Pad41)") (class "Default")
      (node (ref "U3") (pin "41") (pinfunction "PB5_41") (pintype "bidirectional"))
    )
    (net (code "76") (name "unconnected-(U3A-PB14-Pad27)") (class "Default")
      (node (ref "U3") (pin "27") (pinfunction "PB14_27") (pintype "bidirectional"))
    )
    (net (code "77") (name "unconnected-(U3A-PC13-TAMPER-RTC-Pad2)") (class "Default")
      (node (ref "U3") (pin "2") (pinfunction "PC13-TAMPER-RTC_2") (pintype "bidirectional"))
    )
    (net (code "78") (name "unconnected-(U3A-PC14-OSC32_IN-Pad3)") (class "Default")
      (node (ref "U3") (pin "3") (pinfunction "PC14-OSC32_IN_3") (pintype "bidirectional+no_connect"))
    )
    (net (code "79") (name "unconnected-(U3A-PC15-OSC32_OUT-Pad4)") (class "Default")
      (node (ref "U3") (pin "4") (pinfunction "PC15-OSC32_OUT_4") (pintype "bidirectional+no_connect"))
    )
    (net (code "80") (name "unconnected-(U4-COMPN-Pad13)") (class "Default")
      (node (ref "U4") (pin "13") (pinfunction "COMPN_13") (pintype "input+no_connect"))
    )
    (net (code "81") (name "unconnected-(U4-COMPP-Pad12)") (class "Default")
      (node (ref "U4") (pin "12") (pinfunction "COMPP_12") (pintype "input+no_connect"))
    )
    (net (code "82") (name "unconnected-(U4-NC-Pad21)") (class "Default")
      (node (ref "U4") (pin "21") (pinfunction "NC_21") (pintype "passive+no_connect"))
    )
    (net (code "83") (name "unconnected-(U4-V3P3-Pad15)") (class "Default")
      (node (ref "U4") (pin "15") (pinfunction "V3P3_15") (pintype "power_in+no_connect"))
    )
    (net (code "84") (name "unconnected-(U4-~{COMPO}-Pad19)") (class "Default")
      (node (ref "U4") (pin "19") (pinfunction "~{COMPO}_19") (pintype "open_collector+no_connect"))
    )
    (net (code "85") (name "unconnected-(U8-VREF-Pad5)") (class "Default")
      (node (ref "U8") (pin "5") (pinfunction "VREF_5") (pintype "output+no_connect"))
    )
    (net (code "86") (name "unconnected-(U9-RTS#-Pad4)") (class "Default")
      (node (ref "U9") (pin "4") (pinfunction "RTS#_4") (pintype "passive+no_connect"))
    )
    (net (code "87") (name "unconnected-(USBC1-Pad0)") (class "Default")
      (node (ref "USBC1") (pin "0") (pinfunction "0_0") (pintype "passive+no_connect"))
    )
    (net (code "88") (name "unconnected-(USBC1-Pad0)_1") (class "Default")
      (node (ref "USBC1") (pin "0") (pinfunction "0_0") (pintype "passive+no_connect"))
    )
    (net (code "89") (name "unconnected-(USBC1-Pad0)_2") (class "Default")
      (node (ref "USBC1") (pin "0") (pinfunction "0_0") (pintype "passive+no_connect"))
    )
    (net (code "90") (name "unconnected-(USBC1-Pad0)_3") (class "Default")
      (node (ref "USBC1") (pin "0") (pinfunction "0_0") (pintype "passive+no_connect"))
    )
    (net (code "91") (name "unconnected-(USBC1-SBU1-PadA8)") (class "Default")
      (node (ref "USBC1") (pin "A8") (pinfunction "SBU1_A8") (pintype "passive+no_connect"))
    )
    (net (code "92") (name "unconnected-(USBC1-SBU2-PadB8)") (class "Default")
      (node (ref "USBC1") (pin "B8") (pinfunction "SBU2_B8") (pintype "passive+no_connect"))
    )
  )
)
